# probe.net
KiCad netlist of a schematic drawn in EAGLE
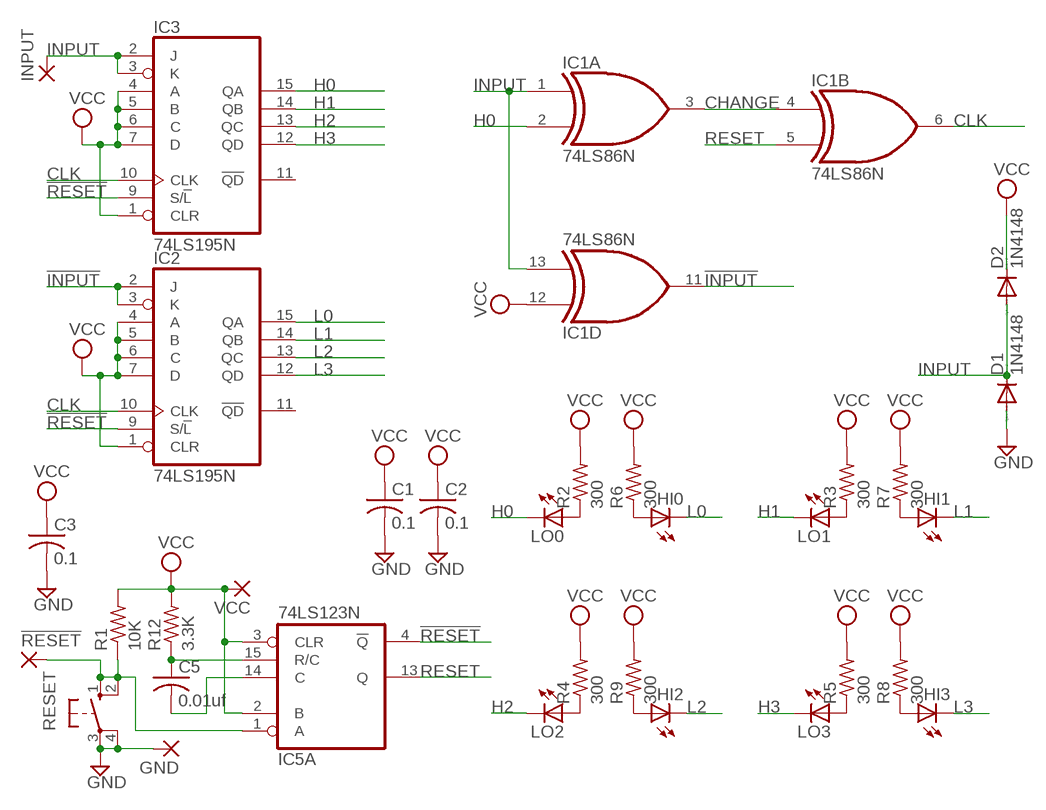
[diagram p0: schematic, sheet 1]

(export (version "E")
  (design (tool "Eeschema 10.0.6"))
  (components
    (comp (ref "!RESET")
      (value "2,15/1,0")
      (footprint "eagle-import:2,15_1,0")
      (libsource (lib "eagle-import") (part "2,15/1,0"))
    )
    (comp (ref "C1")
      (value "0.1")
      (footprint "eagle-import:C050-025X075")
      (libsource (lib "eagle-import") (part "C-US050-025X075"))
    )
    (comp (ref "C2")
      (value "0.1")
      (footprint "eagle-import:C050-025X075")
      (libsource (lib "eagle-import") (part "C-US050-025X075"))
    )
    (comp (ref "C3")
      (value "0.1")
      (footprint "eagle-import:C050-025X075")
      (libsource (lib "eagle-import") (part "C-US050-025X075"))
    )
    (comp (ref "C5")
      (value "0.01uf")
      (footprint "eagle-import:C050-025X075")
      (libsource (lib "eagle-import") (part "C-US050-025X075"))
    )
    (comp (ref "D1")
      (value "1N4148")
      (footprint "eagle-import:DO35-10")
      (libsource (lib "eagle-import") (part "1N4148DO35-10"))
    )
    (comp (ref "D2")
      (value "1N4148")
      (footprint "eagle-import:DO35-10")
      (libsource (lib "eagle-import") (part "1N4148DO35-10"))
    )
    (comp (ref "GND")
      (value "2,15/1,0")
      (footprint "eagle-import:2,15_1,0")
      (libsource (lib "eagle-import") (part "2,15/1,0"))
    )
    (comp (ref "HI0")
      (value "LED3MM")
      (footprint "eagle-import:LED3MM")
      (libsource (lib "eagle-import") (part "LED3MM"))
    )
    (comp (ref "HI1")
      (value "LED3MM")
      (footprint "eagle-import:LED3MM")
      (libsource (lib "eagle-import") (part "LED3MM"))
    )
    (comp (ref "HI2")
      (value "LED3MM")
      (footprint "eagle-import:LED3MM")
      (libsource (lib "eagle-import") (part "LED3MM"))
    )
    (comp (ref "HI3")
      (value "LED3MM")
      (footprint "eagle-import:LED3MM")
      (libsource (lib "eagle-import") (part "LED3MM"))
    )
    (comp (ref "IC1")
      (value "74LS86N")
      (footprint "eagle-import:DIL14")
      (libsource (lib "eagle-import") (part "7486NLS"))
    )
    (comp (ref "IC2")
      (value "74LS195N")
      (footprint "eagle-import:DIL16")
      (libsource (lib "eagle-import") (part "74195NLS"))
    )
    (comp (ref "IC3")
      (value "74LS195N")
      (footprint "eagle-import:DIL16")
      (libsource (lib "eagle-import") (part "74195NLS"))
    )
    (comp (ref "IC5")
      (value "74LS123N")
      (footprint "eagle-import:DIL16")
      (libsource (lib "eagle-import") (part "74123NLS"))
    )
    (comp (ref "INPUT")
      (value "2,15/1,0")
      (footprint "eagle-import:2,15_1,0")
      (libsource (lib "eagle-import") (part "2,15/1,0"))
    )
    (comp (ref "LO0")
      (value "LED3MM")
      (footprint "eagle-import:LED3MM")
      (libsource (lib "eagle-import") (part "LED3MM"))
    )
    (comp (ref "LO1")
      (value "LED3MM")
      (footprint "eagle-import:LED3MM")
      (libsource (lib "eagle-import") (part "LED3MM"))
    )
    (comp (ref "LO2")
      (value "LED3MM")
      (footprint "eagle-import:LED3MM")
      (libsource (lib "eagle-import") (part "LED3MM"))
    )
    (comp (ref "LO3")
      (value "LED3MM")
      (footprint "eagle-import:LED3MM")
      (libsource (lib "eagle-import") (part "LED3MM"))
    )
    (comp (ref "R1")
      (value "10K")
      (footprint "eagle-import:0207_10")
      (libsource (lib "eagle-import") (part "R-US_0207/10"))
    )
    (comp (ref "R2")
      (value "300")
      (footprint "eagle-import:0207_10")
      (libsource (lib "eagle-import") (part "R-US_0207/10"))
    )
    (comp (ref "R3")
      (value "300")
      (footprint "eagle-import:0207_10")
      (libsource (lib "eagle-import") (part "R-US_0207/10"))
    )
    (comp (ref "R4")
      (value "300")
      (footprint "eagle-import:0207_10")
      (libsource (lib "eagle-import") (part "R-US_0207/10"))
    )
    (comp (ref "R5")
      (value "300")
      (footprint "eagle-import:0207_10")
      (libsource (lib "eagle-import") (part "R-US_0207/10"))
    )
    (comp (ref "R6")
      (value "300")
      (footprint "eagle-import:0207_10")
      (libsource (lib "eagle-import") (part "R-US_0207/10"))
    )
    (comp (ref "R7")
      (value "300")
      (footprint "eagle-import:0207_10")
      (libsource (lib "eagle-import") (part "R-US_0207/10"))
    )
    (comp (ref "R8")
      (value "300")
      (footprint "eagle-import:0207_10")
      (libsource (lib "eagle-import") (part "R-US_0207/10"))
    )
    (comp (ref "R9")
      (value "300")
      (footprint "eagle-import:0207_10")
      (libsource (lib "eagle-import") (part "R-US_0207/10"))
    )
    (comp (ref "R12")
      (value "3.3K")
      (footprint "eagle-import:0207_10")
      (libsource (lib "eagle-import") (part "R-US_0207/10"))
    )
    (comp (ref "RESET")
      (value "40-XX")
      (footprint "eagle-import:B3F-40XX")
      (fields (field (name "MF") "OMRON COMPONENTS USA") (field (name "MPN") "B3F-4000"))
      (libsource (lib "eagle-import") (part "40-XX"))
    )
    (comp (ref "VCC")
      (value "2,15/1,0")
      (footprint "eagle-import:2,15_1,0")
      (libsource (lib "eagle-import") (part "2,15/1,0"))
    )
  )
  (nets
    (net (code "1") (name "/CHANGE") (class "Default")
      (node (ref "IC1") (pin "3") (pinfunction "O_3") (pintype "output"))
      (node (ref "IC1") (pin "4") (pinfunction "I0_4") (pintype "input"))
    )
    (net (code "2") (name "/CLK") (class "Default")
      (node (ref "IC1") (pin "6") (pinfunction "O_6") (pintype "output"))
      (node (ref "IC2") (pin "10") (pinfunction "CLK_10") (pintype "input"))
      (node (ref "IC3") (pin "10") (pinfunction "CLK_10") (pintype "input"))
    )
    (net (code "3") (name "/H0") (class "Default")
      (node (ref "IC1") (pin "2") (pinfunction "I1_2") (pintype "input"))
      (node (ref "IC3") (pin "15") (pinfunction "QA_15") (pintype "output"))
      (node (ref "LO0") (pin "K") (pinfunction "C_K") (pintype "passive"))
    )
    (net (code "4") (name "/H1") (class "Default")
      (node (ref "IC3") (pin "14") (pinfunction "QB_14") (pintype "output"))
      (node (ref "LO1") (pin "K") (pinfunction "C_K") (pintype "passive"))
    )
    (net (code "5") (name "/H2") (class "Default")
      (node (ref "IC3") (pin "13") (pinfunction "QC_13") (pintype "output"))
      (node (ref "LO2") (pin "K") (pinfunction "C_K") (pintype "passive"))
    )
    (net (code "6") (name "/H3") (class "Default")
      (node (ref "IC3") (pin "12") (pinfunction "QD_12") (pintype "output"))
      (node (ref "LO3") (pin "K") (pinfunction "C_K") (pintype "passive"))
    )
    (net (code "7") (name "/INPUT") (class "Default")
      (node (ref "D1") (pin "C") (pinfunction "C_C") (pintype "passive"))
      (node (ref "D2") (pin "A") (pinfunction "A_A") (pintype "passive"))
      (node (ref "IC1") (pin "1") (pinfunction "I0_1") (pintype "input"))
      (node (ref "IC1") (pin "13") (pinfunction "I1_13") (pintype "input"))
      (node (ref "IC3") (pin "2") (pinfunction "J_2") (pintype "input"))
      (node (ref "IC3") (pin "3") (pinfunction "K_3") (pintype "input"))
      (node (ref "INPUT") (pin "1") (pinfunction "P_1") (pintype "passive"))
    )
    (net (code "8") (name "/L0") (class "Default")
      (node (ref "HI0") (pin "K") (pinfunction "C_K") (pintype "passive"))
      (node (ref "IC2") (pin "15") (pinfunction "QA_15") (pintype "output"))
    )
    (net (code "9") (name "/L1") (class "Default")
      (node (ref "HI1") (pin "K") (pinfunction "C_K") (pintype "passive"))
      (node (ref "IC2") (pin "14") (pinfunction "QB_14") (pintype "output"))
    )
    (net (code "10") (name "/L2") (class "Default")
      (node (ref "HI2") (pin "K") (pinfunction "C_K") (pintype "passive"))
      (node (ref "IC2") (pin "13") (pinfunction "QC_13") (pintype "output"))
    )
    (net (code "11") (name "/L3") (class "Default")
      (node (ref "HI3") (pin "K") (pinfunction "C_K") (pintype "passive"))
      (node (ref "IC2") (pin "12") (pinfunction "QD_12") (pintype "output"))
    )
    (net (code "12") (name "/RESET") (class "Default")
      (node (ref "IC1") (pin "5") (pinfunction "I1_5") (pintype "input"))
      (node (ref "IC5") (pin "13") (pinfunction "Q_13") (pintype "output"))
    )
    (net (code "13") (name "/~{INPUT}") (class "Default")
      (node (ref "IC1") (pin "11") (pinfunction "O_11") (pintype "output"))
      (node (ref "IC2") (pin "2") (pinfunction "J_2") (pintype "input"))
      (node (ref "IC2") (pin "3") (pinfunction "K_3") (pintype "input"))
    )
    (net (code "14") (name "/~{RESET}") (class "Default")
      (node (ref "IC2") (pin "9") (pinfunction "S/~{L}_9") (pintype "input"))
      (node (ref "IC3") (pin "9") (pinfunction "S/~{L}_9") (pintype "input"))
      (node (ref "IC5") (pin "4") (pinfunction "~{Q}_4") (pintype "output"))
    )
    (net (code "15") (name "GND") (class "Default")
      (node (ref "C1") (pin "2") (pinfunction "2_2") (pintype "passive"))
      (node (ref "C2") (pin "2") (pinfunction "2_2") (pintype "passive"))
      (node (ref "C3") (pin "2") (pinfunction "2_2") (pintype "passive"))
      (node (ref "D1") (pin "A") (pinfunction "A_A") (pintype "passive"))
      (node (ref "GND") (pin "1") (pinfunction "P_1") (pintype "passive"))
      (node (ref "RESET") (pin "3") (pinfunction "P_3") (pintype "passive"))
      (node (ref "RESET") (pin "4") (pinfunction "P1_4") (pintype "passive"))
    )
    (net (code "16") (name "Net-(!RESET-P)") (class "Default")
      (node (ref "!RESET") (pin "1") (pinfunction "P_1") (pintype "passive"))
      (node (ref "IC5") (pin "1") (pinfunction "A_1") (pintype "input"))
      (node (ref "R1") (pin "1") (pinfunction "1_1") (pintype "passive"))
      (node (ref "RESET") (pin "1") (pinfunction "S_1") (pintype "passive"))
      (node (ref "RESET") (pin "2") (pinfunction "S1_2") (pintype "passive"))
    )
    (net (code "17") (name "Net-(HI0-PadA)") (class "Default")
      (node (ref "HI0") (pin "A") (pinfunction "A_A") (pintype "passive"))
      (node (ref "R6") (pin "1") (pinfunction "1_1") (pintype "passive"))
    )
    (net (code "18") (name "Net-(HI1-PadA)") (class "Default")
      (node (ref "HI1") (pin "A") (pinfunction "A_A") (pintype "passive"))
      (node (ref "R7") (pin "1") (pinfunction "1_1") (pintype "passive"))
    )
    (net (code "19") (name "Net-(HI2-PadA)") (class "Default")
      (node (ref "HI2") (pin "A") (pinfunction "A_A") (pintype "passive"))
      (node (ref "R9") (pin "1") (pinfunction "1_1") (pintype "passive"))
    )
    (net (code "20") (name "Net-(HI3-PadA)") (class "Default")
      (node (ref "HI3") (pin "A") (pinfunction "A_A") (pintype "passive"))
      (node (ref "R8") (pin "1") (pinfunction "1_1") (pintype "passive"))
    )
    (net (code "21") (name "Net-(IC5A-C)") (class "Default")
      (node (ref "C5") (pin "2") (pinfunction "2_2") (pintype "passive"))
      (node (ref "IC5") (pin "14") (pinfunction "C_14") (pintype "input"))
    )
    (net (code "22") (name "Net-(IC5A-R{slash}C)") (class "Default")
      (node (ref "C5") (pin "1") (pinfunction "1_1") (pintype "passive"))
      (node (ref "IC5") (pin "15") (pinfunction "R/C_15") (pintype "input"))
      (node (ref "R12") (pin "1") (pinfunction "1_1") (pintype "passive"))
    )
    (net (code "23") (name "Net-(LO0-PadA)") (class "Default")
      (node (ref "LO0") (pin "A") (pinfunction "A_A") (pintype "passive"))
      (node (ref "R2") (pin "1") (pinfunction "1_1") (pintype "passive"))
    )
    (net (code "24") (name "Net-(LO1-PadA)") (class "Default")
      (node (ref "LO1") (pin "A") (pinfunction "A_A") (pintype "passive"))
      (node (ref "R3") (pin "1") (pinfunction "1_1") (pintype "passive"))
    )
    (net (code "25") (name "Net-(LO2-PadA)") (class "Default")
      (node (ref "LO2") (pin "A") (pinfunction "A_A") (pintype "passive"))
      (node (ref "R4") (pin "1") (pinfunction "1_1") (pintype "passive"))
    )
    (net (code "26") (name "Net-(LO3-PadA)") (class "Default")
      (node (ref "LO3") (pin "A") (pinfunction "A_A") (pintype "passive"))
      (node (ref "R5") (pin "1") (pinfunction "1_1") (pintype "passive"))
    )
    (net (code "27") (name "VCC") (class "Default")
      (node (ref "C1") (pin "1") (pinfunction "1_1") (pintype "passive"))
      (node (ref "C2") (pin "1") (pinfunction "1_1") (pintype "passive"))
      (node (ref "C3") (pin "1") (pinfunction "1_1") (pintype "passive"))
      (node (ref "D2") (pin "C") (pinfunction "C_C") (pintype "passive"))
      (node (ref "IC1") (pin "12") (pinfunction "I0_12") (pintype "input"))
      (node (ref "IC2") (pin "1") (pinfunction "CLR_1") (pintype "input"))
      (node (ref "IC2") (pin "4") (pinfunction "A_4") (pintype "input"))
      (node (ref "IC2") (pin "5") (pinfunction "B_5") (pintype "input"))
      (node (ref "IC2") (pin "6") (pinfunction "C_6") (pintype "input"))
      (node (ref "IC2") (pin "7") (pinfunction "D_7") (pintype "input"))
      (node (ref "IC3") (pin "1") (pinfunction "CLR_1") (pintype "input"))
      (node (ref "IC3") (pin "4") (pinfunction "A_4") (pintype "input"))
      (node (ref "IC3") (pin "5") (pinfunction "B_5") (pintype "input"))
      (node (ref "IC3") (pin "6") (pinfunction "C_6") (pintype "input"))
      (node (ref "IC3") (pin "7") (pinfunction "D_7") (pintype "input"))
      (node (ref "IC5") (pin "2") (pinfunction "B_2") (pintype "input"))
      (node (ref "IC5") (pin "3") (pinfunction "CLR_3") (pintype "input"))
      (node (ref "R1") (pin "2") (pinfunction "2_2") (pintype "passive"))
      (node (ref "R12") (pin "2") (pinfunction "2_2") (pintype "passive"))
      (node (ref "R2") (pin "2") (pinfunction "2_2") (pintype "passive"))
      (node (ref "R3") (pin "2") (pinfunction "2_2") (pintype "passive"))
      (node (ref "R4") (pin "2") (pinfunction "2_2") (pintype "passive"))
      (node (ref "R5") (pin "2") (pinfunction "2_2") (pintype "passive"))
      (node (ref "R6") (pin "2") (pinfunction "2_2") (pintype "passive"))
      (node (ref "R7") (pin "2") (pinfunction "2_2") (pintype "passive"))
      (node (ref "R8") (pin "2") (pinfunction "2_2") (pintype "passive"))
      (node (ref "R9") (pin "2") (pinfunction "2_2") (pintype "passive"))
      (node (ref "VCC") (pin "1") (pinfunction "P_1") (pintype "passive"))
    )
    (net (code "28") (name "unconnected-(IC2A-~{QD}-Pad11)") (class "Default")
      (node (ref "IC2") (pin "11") (pinfunction "~{QD}_11") (pintype "output"))
    )
    (net (code "29") (name "unconnected-(IC3A-~{QD}-Pad11)") (class "Default")
      (node (ref "IC3") (pin "11") (pinfunction "~{QD}_11") (pintype "output"))
    )
  )
)
